# ab-berry-rev2-2.net
KiCad netlist of a schematic drawn in EAGLE
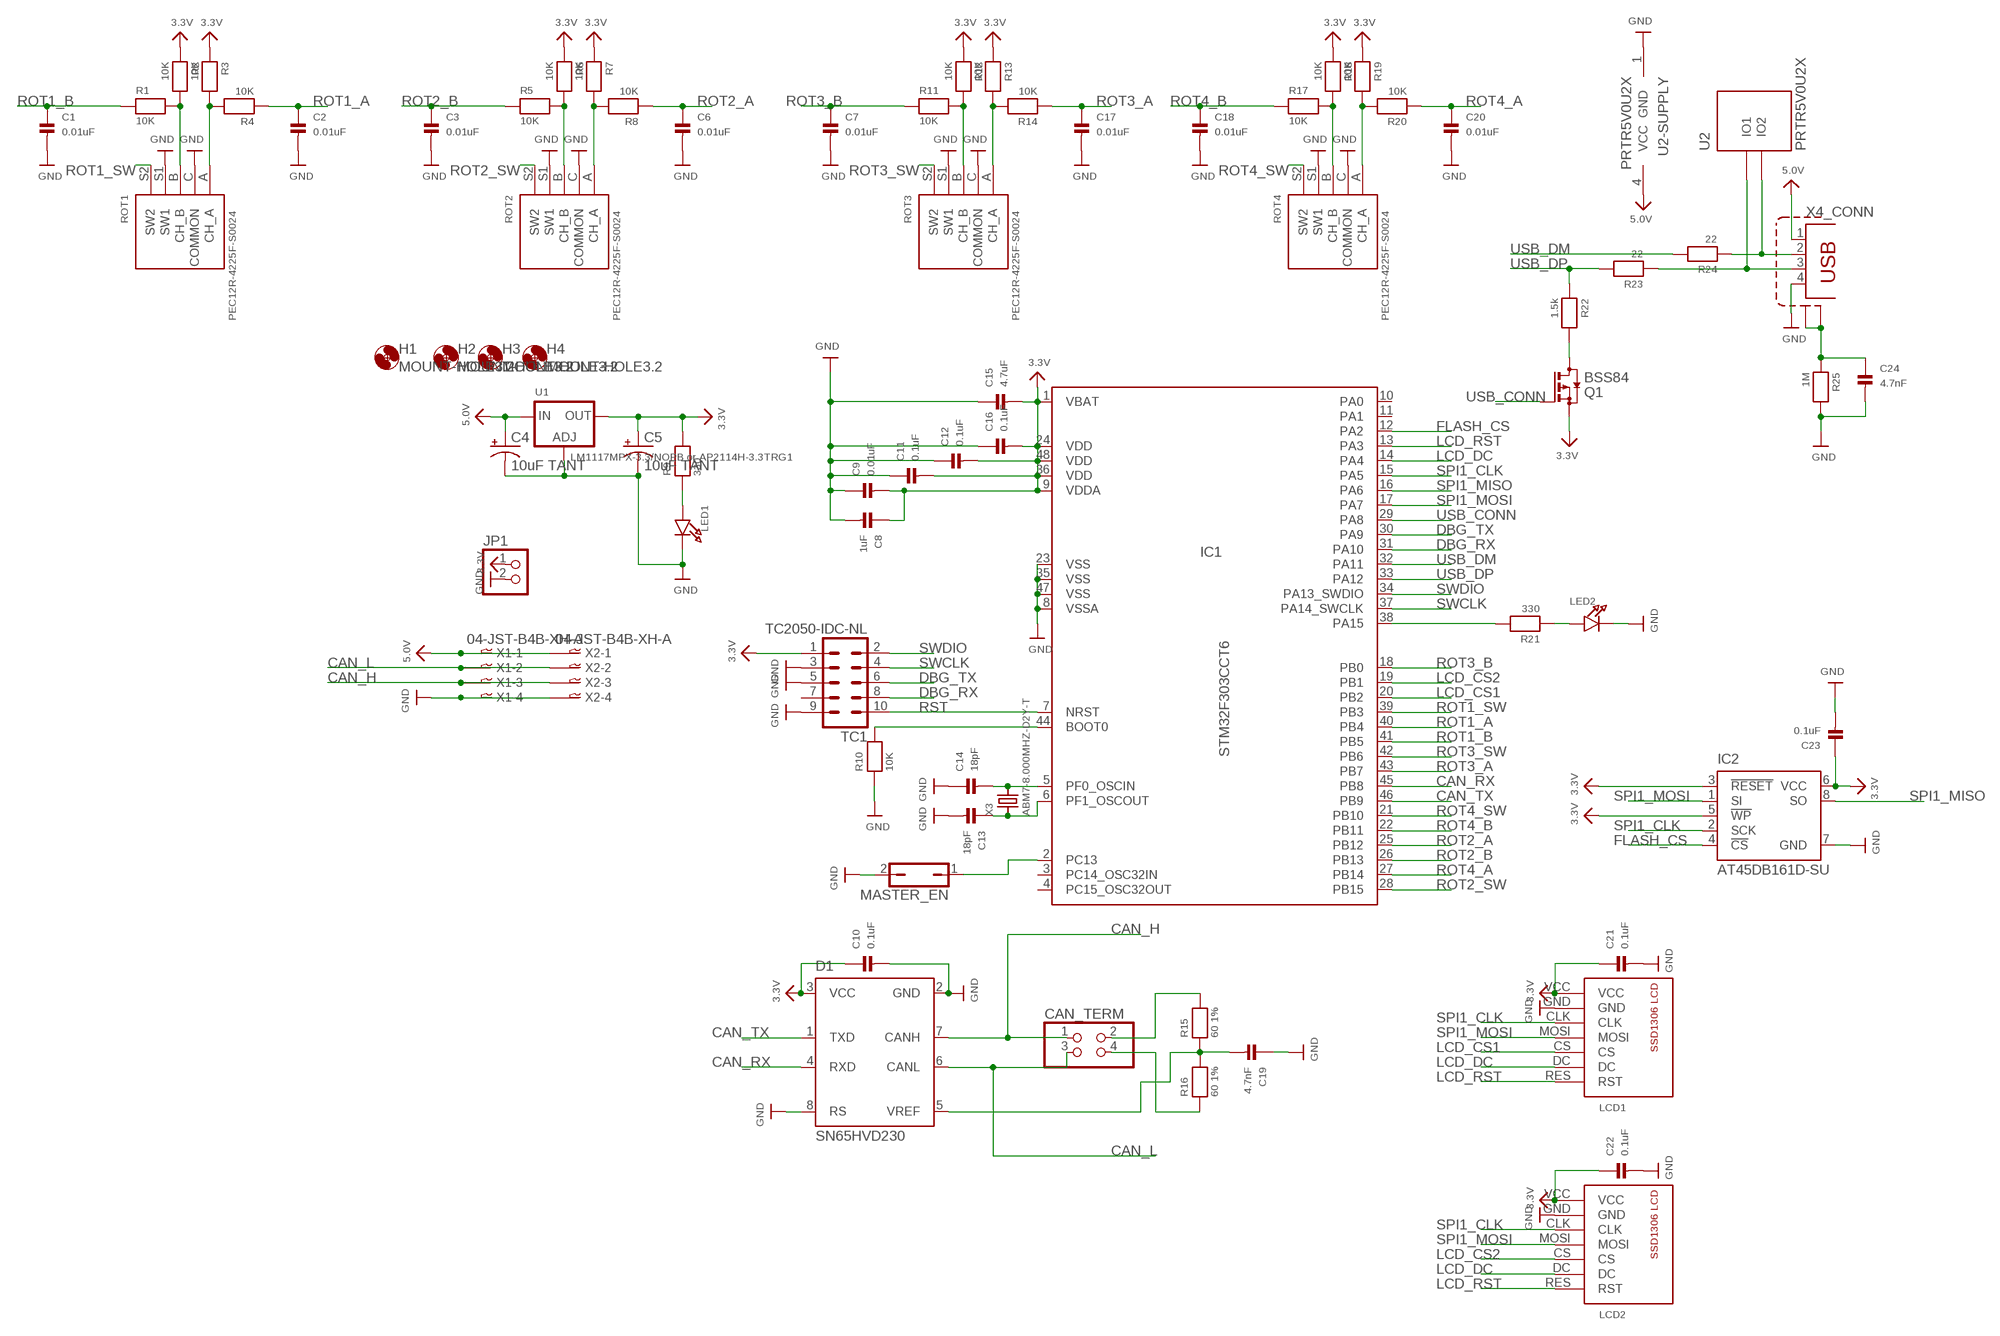
[diagram p0: schematic, sheet 1]

(export (version "E")
  (design (tool "Eeschema 10.0.6"))
  (components
    (comp (ref "C1")
      (value "0.01uF")
      (footprint "eagle-import:0603")
      (libsource (lib "eagle-import") (part "CAP_CERAMIC0603"))
    )
    (comp (ref "C2")
      (value "0.01uF")
      (footprint "eagle-import:0603")
      (libsource (lib "eagle-import") (part "CAP_CERAMIC0603"))
    )
    (comp (ref "C3")
      (value "0.01uF")
      (footprint "eagle-import:0603")
      (libsource (lib "eagle-import") (part "CAP_CERAMIC0603"))
    )
    (comp (ref "C4")
      (value "10uF TANT")
      (footprint "eagle-import:0603-POL")
      (libsource (lib "eagle-import") (part "10UF-6.3V-20%(0603)(TANT){dblquote}"))
    )
    (comp (ref "C5")
      (value "10uF TANT")
      (footprint "eagle-import:0603-POL")
      (libsource (lib "eagle-import") (part "10UF-6.3V-20%(0603)(TANT){dblquote}"))
    )
    (comp (ref "C6")
      (value "0.01uF")
      (footprint "eagle-import:0603")
      (libsource (lib "eagle-import") (part "CAP_CERAMIC0603"))
    )
    (comp (ref "C7")
      (value "0.01uF")
      (footprint "eagle-import:0603")
      (libsource (lib "eagle-import") (part "CAP_CERAMIC0603"))
    )
    (comp (ref "C8")
      (value "1uF")
      (footprint "eagle-import:0603")
      (libsource (lib "eagle-import") (part "CAP_CERAMIC0603"))
    )
    (comp (ref "C9")
      (value "0.01uF")
      (footprint "eagle-import:0603")
      (libsource (lib "eagle-import") (part "CAP_CERAMIC0603"))
    )
    (comp (ref "C10")
      (value "0.1uF")
      (footprint "eagle-import:0603")
      (libsource (lib "eagle-import") (part "CAP_CERAMIC0603"))
    )
    (comp (ref "C11")
      (value "0.1uF")
      (footprint "eagle-import:0603")
      (libsource (lib "eagle-import") (part "CAP_CERAMIC0603"))
    )
    (comp (ref "C12")
      (value "0.1uF")
      (footprint "eagle-import:0603")
      (libsource (lib "eagle-import") (part "CAP_CERAMIC0603"))
    )
    (comp (ref "C13")
      (value "18pF")
      (footprint "eagle-import:0603")
      (libsource (lib "eagle-import") (part "CAP_CERAMIC0603"))
    )
    (comp (ref "C14")
      (value "18pF")
      (footprint "eagle-import:0603")
      (libsource (lib "eagle-import") (part "CAP_CERAMIC0603"))
    )
    (comp (ref "C15")
      (value "4.7uF")
      (footprint "eagle-import:0603")
      (libsource (lib "eagle-import") (part "CAP_CERAMIC0603"))
    )
    (comp (ref "C16")
      (value "0.1uF")
      (footprint "eagle-import:0603")
      (libsource (lib "eagle-import") (part "CAP_CERAMIC0603"))
    )
    (comp (ref "C17")
      (value "0.01uF")
      (footprint "eagle-import:0603")
      (libsource (lib "eagle-import") (part "CAP_CERAMIC0603"))
    )
    (comp (ref "C18")
      (value "0.01uF")
      (footprint "eagle-import:0603")
      (libsource (lib "eagle-import") (part "CAP_CERAMIC0603"))
    )
    (comp (ref "C19")
      (value "4.7nF")
      (footprint "eagle-import:0603")
      (libsource (lib "eagle-import") (part "CAP_CERAMIC0603"))
    )
    (comp (ref "C20")
      (value "0.01uF")
      (footprint "eagle-import:0603")
      (libsource (lib "eagle-import") (part "CAP_CERAMIC0603"))
    )
    (comp (ref "C21")
      (value "0.1uF")
      (footprint "eagle-import:0603")
      (libsource (lib "eagle-import") (part "CAP_CERAMIC0603"))
    )
    (comp (ref "C22")
      (value "0.1uF")
      (footprint "eagle-import:0603")
      (libsource (lib "eagle-import") (part "CAP_CERAMIC0603"))
    )
    (comp (ref "C23")
      (value "0.1uF")
      (footprint "eagle-import:0603")
      (libsource (lib "eagle-import") (part "CAP_CERAMIC0603"))
    )
    (comp (ref "C24")
      (value "4.7nF")
      (footprint "eagle-import:0603")
      (libsource (lib "eagle-import") (part "CAP_CERAMIC0603"))
    )
    (comp (ref "CAN_TERM")
      (value "PINHD-2X2")
      (footprint "eagle-import:2X02")
      (libsource (lib "eagle-import") (part "PINHD-2X2"))
    )
    (comp (ref "D1")
      (value "SN65HVD230")
      (footprint "eagle-import:SO8")
      (libsource (lib "eagle-import") (part "SN65HVD230"))
    )
    (comp (ref "H1")
      (value "MOUNT-HOLE3.2")
      (footprint "eagle-import:3,2")
      (libsource (lib "eagle-import") (part "MOUNT-HOLE3.2"))
    )
    (comp (ref "H2")
      (value "MOUNT-HOLE3.2")
      (footprint "eagle-import:3,2")
      (libsource (lib "eagle-import") (part "MOUNT-HOLE3.2"))
    )
    (comp (ref "H3")
      (value "MOUNT-HOLE3.2")
      (footprint "eagle-import:3,2")
      (libsource (lib "eagle-import") (part "MOUNT-HOLE3.2"))
    )
    (comp (ref "H4")
      (value "MOUNT-HOLE3.2")
      (footprint "eagle-import:3,2")
      (libsource (lib "eagle-import") (part "MOUNT-HOLE3.2"))
    )
    (comp (ref "IC1")
      (value "STM32F303CCT6")
      (footprint "eagle-import:TQFP48")
      (libsource (lib "eagle-import") (part "STM32F302_F303_B_C_LQFP48"))
    )
    (comp (ref "IC2")
      (value "AT45DB161D-SU")
      (footprint "eagle-import:8S2")
      (fields (field (name "MF") "ATMEL"))
      (libsource (lib "eagle-import") (part "AT45DB161D-SU"))
    )
    (comp (ref "JP1")
      (value "PINHD-1X2")
      (footprint "eagle-import:1X02")
      (libsource (lib "eagle-import") (part "PINHD-1X2"))
    )
    (comp (ref "LCD1")
      (value "SSD1306-7PINWITHOUT-HOLES")
      (footprint "eagle-import:SSD1306-7PIN-NO-HOLES")
      (libsource (lib "eagle-import") (part "SSD1306-7PINWITHOUT-HOLES"))
    )
    (comp (ref "LCD2")
      (value "SSD1306-7PINWITHOUT-HOLES")
      (footprint "eagle-import:SSD1306-7PIN-NO-HOLES")
      (libsource (lib "eagle-import") (part "SSD1306-7PINWITHOUT-HOLES"))
    )
    (comp (ref "LED1")
      (value "LED0603")
      (footprint "eagle-import:CHIPLED_0603")
      (libsource (lib "eagle-import") (part "LED0603"))
    )
    (comp (ref "LED2")
      (value "LED0603")
      (footprint "eagle-import:CHIPLED_0603")
      (libsource (lib "eagle-import") (part "LED0603"))
    )
    (comp (ref "MASTER_EN")
      (value "JP1Q")
      (footprint "eagle-import:JP1")
      (libsource (lib "eagle-import") (part "JP1Q"))
    )
    (comp (ref "Q1")
      (value "BSS84")
      (footprint "eagle-import:SOT23")
      (libsource (lib "eagle-import") (part "BSS84"))
    )
    (comp (ref "R1")
      (value "10K")
      (footprint "eagle-import:0603")
      (libsource (lib "eagle-import") (part "RESISTOR0603"))
    )
    (comp (ref "R2")
      (value "10K")
      (footprint "eagle-import:0603")
      (libsource (lib "eagle-import") (part "RESISTOR0603"))
    )
    (comp (ref "R3")
      (value "10K")
      (footprint "eagle-import:0603")
      (libsource (lib "eagle-import") (part "RESISTOR0603"))
    )
    (comp (ref "R4")
      (value "10K")
      (footprint "eagle-import:0603")
      (libsource (lib "eagle-import") (part "RESISTOR0603"))
    )
    (comp (ref "R5")
      (value "10K")
      (footprint "eagle-import:0603")
      (libsource (lib "eagle-import") (part "RESISTOR0603"))
    )
    (comp (ref "R6")
      (value "10K")
      (footprint "eagle-import:0603")
      (libsource (lib "eagle-import") (part "RESISTOR0603"))
    )
    (comp (ref "R7")
      (value "10K")
      (footprint "eagle-import:0603")
      (libsource (lib "eagle-import") (part "RESISTOR0603"))
    )
    (comp (ref "R8")
      (value "10K")
      (footprint "eagle-import:0603")
      (libsource (lib "eagle-import") (part "RESISTOR0603"))
    )
    (comp (ref "R9")
      (value "330")
      (footprint "eagle-import:0603")
      (libsource (lib "eagle-import") (part "RESISTOR0603"))
    )
    (comp (ref "R10")
      (value "10K")
      (footprint "eagle-import:0603")
      (libsource (lib "eagle-import") (part "RESISTOR0603"))
    )
    (comp (ref "R11")
      (value "10K")
      (footprint "eagle-import:0603")
      (libsource (lib "eagle-import") (part "RESISTOR0603"))
    )
    (comp (ref "R12")
      (value "10K")
      (footprint "eagle-import:0603")
      (libsource (lib "eagle-import") (part "RESISTOR0603"))
    )
    (comp (ref "R13")
      (value "10K")
      (footprint "eagle-import:0603")
      (libsource (lib "eagle-import") (part "RESISTOR0603"))
    )
    (comp (ref "R14")
      (value "10K")
      (footprint "eagle-import:0603")
      (libsource (lib "eagle-import") (part "RESISTOR0603"))
    )
    (comp (ref "R15")
      (value "60 1%")
      (footprint "eagle-import:0603")
      (libsource (lib "eagle-import") (part "RESISTOR0603"))
    )
    (comp (ref "R16")
      (value "60 1%")
      (footprint "eagle-import:0603")
      (libsource (lib "eagle-import") (part "RESISTOR0603"))
    )
    (comp (ref "R17")
      (value "10K")
      (footprint "eagle-import:0603")
      (libsource (lib "eagle-import") (part "RESISTOR0603"))
    )
    (comp (ref "R18")
      (value "10K")
      (footprint "eagle-import:0603")
      (libsource (lib "eagle-import") (part "RESISTOR0603"))
    )
    (comp (ref "R19")
      (value "10K")
      (footprint "eagle-import:0603")
      (libsource (lib "eagle-import") (part "RESISTOR0603"))
    )
    (comp (ref "R20")
      (value "10K")
      (footprint "eagle-import:0603")
      (libsource (lib "eagle-import") (part "RESISTOR0603"))
    )
    (comp (ref "R21")
      (value "330")
      (footprint "eagle-import:0603")
      (libsource (lib "eagle-import") (part "RESISTOR0603"))
    )
    (comp (ref "R22")
      (value "1.5k")
      (footprint "eagle-import:0603")
      (libsource (lib "eagle-import") (part "RESISTOR0603"))
    )
    (comp (ref "R23")
      (value "22")
      (footprint "eagle-import:0603")
      (libsource (lib "eagle-import") (part "RESISTOR0603"))
    )
    (comp (ref "R24")
      (value "22")
      (footprint "eagle-import:0603")
      (libsource (lib "eagle-import") (part "RESISTOR0603"))
    )
    (comp (ref "R25")
      (value "1M")
      (footprint "eagle-import:0603")
      (libsource (lib "eagle-import") (part "RESISTOR0603"))
    )
    (comp (ref "ROT1")
      (value "PEC12R-4225F-S0024")
      (footprint "eagle-import:PEC111-4XXXK-SXXXX")
      (libsource (lib "eagle-import") (part "PEC11-4215K-S0024"))
    )
    (comp (ref "ROT2")
      (value "PEC12R-4225F-S0024")
      (footprint "eagle-import:PEC111-4XXXK-SXXXX")
      (libsource (lib "eagle-import") (part "PEC11-4215K-S0024"))
    )
    (comp (ref "ROT3")
      (value "PEC12R-4225F-S0024")
      (footprint "eagle-import:PEC111-4XXXK-SXXXX")
      (libsource (lib "eagle-import") (part "PEC11-4215K-S0024"))
    )
    (comp (ref "ROT4")
      (value "PEC12R-4225F-S0024")
      (footprint "eagle-import:PEC111-4XXXK-SXXXX")
      (libsource (lib "eagle-import") (part "PEC11-4215K-S0024"))
    )
    (comp (ref "TC1")
      (value "TC2050-IDC-NL")
      (footprint "eagle-import:TC2050-IDC-NL")
      (libsource (lib "eagle-import") (part "TC2050-IDC-NL"))
    )
    (comp (ref "U1")
      (value "LM1117MPX-3.3/NOPB or AP2114H-3.3TRG1")
      (footprint "eagle-import:SOT223-R")
      (fields (field (name "MPN") "LM1117MPX-3.3/NOPB"))
      (libsource (lib "eagle-import") (part "LM1117SOT223-REFLOW"))
    )
    (comp (ref "U2")
      (value "PRTR5V0U2X")
      (footprint "eagle-import:SOT-143B")
      (fields
        (field (name "MANUFACTURER") "NXP Semiconductors")
        (field (name "PART_NUMBER") "PRTR5V0U2X,215")
      )
      (libsource (lib "eagle-import") (part "PRTR5V0U2X?"))
    )
    (comp (ref "X1")
      (value "04-JST-B4B-XH-A")
      (footprint "eagle-import:B4B-XH")
      (libsource (lib "eagle-import") (part "04-JST-B4B-XH-A"))
    )
    (comp (ref "X2")
      (value "04-JST-B4B-XH-A")
      (footprint "eagle-import:B4B-XH")
      (libsource (lib "eagle-import") (part "04-JST-B4B-XH-A"))
    )
    (comp (ref "X3")
      (value "ABM7-8.000MHZ-D2Y-T")
      (footprint "eagle-import:ABM7-8.000MHZ-D2Y-T")
      (libsource (lib "eagle-import") (part "ABM7-8.000MHZ-D2Y-T"))
    )
    (comp (ref "X4")
      (value "TE-292304-1")
      (footprint "eagle-import:TE-292304-1")
      (libsource (lib "eagle-import") (part "TE-292304-1"))
    )
  )
  (nets
    (net (code "1") (name "/CAN_H") (class "Default")
      (node (ref "CAN_TERM") (pin "1") (pinfunction "1_1") (pintype "passive"))
      (node (ref "D1") (pin "7") (pinfunction "CANH_7") (pintype "bidirectional"))
      (node (ref "X1") (pin "P$3") (pinfunction "1_P$3") (pintype "passive"))
      (node (ref "X2") (pin "P$3") (pinfunction "1_P$3") (pintype "passive"))
    )
    (net (code "2") (name "/CAN_L") (class "Default")
      (node (ref "CAN_TERM") (pin "3") (pinfunction "3_3") (pintype "passive"))
      (node (ref "D1") (pin "6") (pinfunction "CANL_6") (pintype "bidirectional"))
      (node (ref "X1") (pin "P$2") (pinfunction "1_P$2") (pintype "passive"))
      (node (ref "X2") (pin "P$2") (pinfunction "1_P$2") (pintype "passive"))
    )
    (net (code "3") (name "/CAN_RX") (class "Default")
      (node (ref "D1") (pin "4") (pinfunction "RXD_4") (pintype "output"))
      (node (ref "IC1") (pin "45") (pinfunction "PB8_45") (pintype "bidirectional"))
    )
    (net (code "4") (name "/CAN_TX") (class "Default")
      (node (ref "D1") (pin "1") (pinfunction "TXD_1") (pintype "input"))
      (node (ref "IC1") (pin "46") (pinfunction "PB9_46") (pintype "bidirectional"))
    )
    (net (code "5") (name "/DBG_RX") (class "Default")
      (node (ref "IC1") (pin "31") (pinfunction "PA10_31") (pintype "bidirectional"))
      (node (ref "TC1") (pin "8") (pinfunction "8_8") (pintype "passive"))
    )
    (net (code "6") (name "/DBG_TX") (class "Default")
      (node (ref "IC1") (pin "30") (pinfunction "PA9_30") (pintype "bidirectional"))
      (node (ref "TC1") (pin "6") (pinfunction "6_6") (pintype "passive"))
    )
    (net (code "7") (name "/FLASH_CS") (class "Default")
      (node (ref "IC1") (pin "12") (pinfunction "PA2_12") (pintype "bidirectional"))
      (node (ref "IC2") (pin "4") (pinfunction "~{CS}_4") (pintype "input"))
    )
    (net (code "8") (name "/LCD_CS1") (class "Default")
      (node (ref "IC1") (pin "20") (pinfunction "PB2_20") (pintype "bidirectional"))
      (node (ref "LCD1") (pin "CS") (pinfunction "CS_CS") (pintype "bidirectional"))
    )
    (net (code "9") (name "/LCD_CS2") (class "Default")
      (node (ref "IC1") (pin "19") (pinfunction "PB1_19") (pintype "bidirectional"))
      (node (ref "LCD2") (pin "CS") (pinfunction "CS_CS") (pintype "bidirectional"))
    )
    (net (code "10") (name "/LCD_DC") (class "Default")
      (node (ref "IC1") (pin "14") (pinfunction "PA4_14") (pintype "bidirectional"))
      (node (ref "LCD1") (pin "DC") (pinfunction "DC_DC") (pintype "bidirectional"))
      (node (ref "LCD2") (pin "DC") (pinfunction "DC_DC") (pintype "bidirectional"))
    )
    (net (code "11") (name "/LCD_RST") (class "Default")
      (node (ref "IC1") (pin "13") (pinfunction "PA3_13") (pintype "bidirectional"))
      (node (ref "LCD1") (pin "RES") (pinfunction "RST_RES") (pintype "bidirectional"))
      (node (ref "LCD2") (pin "RES") (pinfunction "RST_RES") (pintype "bidirectional"))
    )
    (net (code "12") (name "/ROT1_A") (class "Default")
      (node (ref "C2") (pin "1") (pinfunction "P$1_1") (pintype "passive"))
      (node (ref "IC1") (pin "40") (pinfunction "PB4_40") (pintype "input"))
      (node (ref "R4") (pin "1") (pinfunction "1_1") (pintype "passive"))
    )
    (net (code "13") (name "/ROT1_B") (class "Default")
      (node (ref "C1") (pin "1") (pinfunction "P$1_1") (pintype "passive"))
      (node (ref "IC1") (pin "41") (pinfunction "PB5_41") (pintype "bidirectional"))
      (node (ref "R1") (pin "1") (pinfunction "1_1") (pintype "passive"))
    )
    (net (code "14") (name "/ROT1_SW") (class "Default")
      (node (ref "IC1") (pin "39") (pinfunction "PB3_39") (pintype "output"))
      (node (ref "ROT1") (pin "S2") (pinfunction "SW2_S2") (pintype "bidirectional"))
    )
    (net (code "15") (name "/ROT2_A") (class "Default")
      (node (ref "C6") (pin "1") (pinfunction "P$1_1") (pintype "passive"))
      (node (ref "IC1") (pin "25") (pinfunction "PB12_25") (pintype "bidirectional"))
      (node (ref "R8") (pin "1") (pinfunction "1_1") (pintype "passive"))
    )
    (net (code "16") (name "/ROT2_B") (class "Default")
      (node (ref "C3") (pin "1") (pinfunction "P$1_1") (pintype "passive"))
      (node (ref "IC1") (pin "26") (pinfunction "PB13_26") (pintype "bidirectional"))
      (node (ref "R5") (pin "1") (pinfunction "1_1") (pintype "passive"))
    )
    (net (code "17") (name "/ROT2_SW") (class "Default")
      (node (ref "IC1") (pin "28") (pinfunction "PB15_28") (pintype "bidirectional"))
      (node (ref "ROT2") (pin "S2") (pinfunction "SW2_S2") (pintype "bidirectional"))
    )
    (net (code "18") (name "/ROT3_A") (class "Default")
      (node (ref "C17") (pin "1") (pinfunction "P$1_1") (pintype "passive"))
      (node (ref "IC1") (pin "43") (pinfunction "PB7_43") (pintype "bidirectional"))
      (node (ref "R14") (pin "1") (pinfunction "1_1") (pintype "passive"))
    )
    (net (code "19") (name "/ROT3_B") (class "Default")
      (node (ref "C7") (pin "1") (pinfunction "P$1_1") (pintype "passive"))
      (node (ref "IC1") (pin "18") (pinfunction "PB0_18") (pintype "bidirectional"))
      (node (ref "R11") (pin "1") (pinfunction "1_1") (pintype "passive"))
    )
    (net (code "20") (name "/ROT3_SW") (class "Default")
      (node (ref "IC1") (pin "42") (pinfunction "PB6_42") (pintype "bidirectional"))
      (node (ref "ROT3") (pin "S2") (pinfunction "SW2_S2") (pintype "bidirectional"))
    )
    (net (code "21") (name "/ROT4_A") (class "Default")
      (node (ref "C20") (pin "1") (pinfunction "P$1_1") (pintype "passive"))
      (node (ref "IC1") (pin "27") (pinfunction "PB14_27") (pintype "bidirectional"))
      (node (ref "R20") (pin "1") (pinfunction "1_1") (pintype "passive"))
    )
    (net (code "22") (name "/ROT4_B") (class "Default")
      (node (ref "C18") (pin "1") (pinfunction "P$1_1") (pintype "passive"))
      (node (ref "IC1") (pin "22") (pinfunction "PB11_22") (pintype "bidirectional"))
      (node (ref "R17") (pin "1") (pinfunction "1_1") (pintype "passive"))
    )
    (net (code "23") (name "/ROT4_SW") (class "Default")
      (node (ref "IC1") (pin "21") (pinfunction "PB10_21") (pintype "bidirectional"))
      (node (ref "ROT4") (pin "S2") (pinfunction "SW2_S2") (pintype "bidirectional"))
    )
    (net (code "24") (name "/RST") (class "Default")
      (node (ref "IC1") (pin "7") (pinfunction "NRST_7") (pintype "input"))
      (node (ref "TC1") (pin "10") (pinfunction "10_10") (pintype "passive"))
    )
    (net (code "25") (name "/SPI1_CLK") (class "Default")
      (node (ref "IC1") (pin "15") (pinfunction "PA5_15") (pintype "bidirectional"))
      (node (ref "IC2") (pin "2") (pinfunction "SCK_2") (pintype "input"))
      (node (ref "LCD1") (pin "CLK") (pinfunction "CLK_CLK") (pintype "bidirectional"))
      (node (ref "LCD2") (pin "CLK") (pinfunction "CLK_CLK") (pintype "bidirectional"))
    )
    (net (code "26") (name "/SPI1_MISO") (class "Default")
      (node (ref "IC1") (pin "16") (pinfunction "PA6_16") (pintype "bidirectional"))
      (node (ref "IC2") (pin "8") (pinfunction "SO_8") (pintype "output"))
    )
    (net (code "27") (name "/SPI1_MOSI") (class "Default")
      (node (ref "IC1") (pin "17") (pinfunction "PA7_17") (pintype "bidirectional"))
      (node (ref "IC2") (pin "1") (pinfunction "SI_1") (pintype "input"))
      (node (ref "LCD1") (pin "MOSI") (pinfunction "MOSI_MOSI") (pintype "bidirectional"))
      (node (ref "LCD2") (pin "MOSI") (pinfunction "MOSI_MOSI") (pintype "bidirectional"))
    )
    (net (code "28") (name "/SWCLK") (class "Default")
      (node (ref "IC1") (pin "37") (pinfunction "PA14_SWCLK_37") (pintype "input"))
      (node (ref "TC1") (pin "4") (pinfunction "4_4") (pintype "passive"))
    )
    (net (code "29") (name "/SWDIO") (class "Default")
      (node (ref "IC1") (pin "34") (pinfunction "PA13_SWDIO_34") (pintype "input"))
      (node (ref "TC1") (pin "2") (pinfunction "2_2") (pintype "passive"))
    )
    (net (code "30") (name "/USB_CONN") (class "Default")
      (node (ref "IC1") (pin "29") (pinfunction "PA8_29") (pintype "bidirectional"))
      (node (ref "Q1") (pin "1") (pinfunction "G_1") (pintype "passive"))
    )
    (net (code "31") (name "/USB_DM") (class "Default")
      (node (ref "IC1") (pin "32") (pinfunction "PA11_32") (pintype "bidirectional"))
      (node (ref "R24") (pin "2") (pinfunction "2_2") (pintype "passive"))
    )
    (net (code "32") (name "/USB_DP") (class "Default")
      (node (ref "IC1") (pin "33") (pinfunction "PA12_33") (pintype "bidirectional"))
      (node (ref "R22") (pin "1") (pinfunction "1_1") (pintype "passive"))
      (node (ref "R23") (pin "2") (pinfunction "2_2") (pintype "passive"))
    )
    (net (code "33") (name "3.3V") (class "Default")
      (node (ref "C10") (pin "1") (pinfunction "P$1_1") (pintype "passive"))
      (node (ref "C11") (pin "2") (pinfunction "P$2_2") (pintype "passive"))
      (node (ref "C12") (pin "2") (pinfunction "P$2_2") (pintype "passive"))
      (node (ref "C15") (pin "2") (pinfunction "P$2_2") (pintype "passive"))
      (node (ref "C16") (pin "2") (pinfunction "P$2_2") (pintype "passive"))
      (node (ref "C21") (pin "1") (pinfunction "P$1_1") (pintype "passive"))
      (node (ref "C22") (pin "1") (pinfunction "P$1_1") (pintype "passive"))
      (node (ref "C23") (pin "1") (pinfunction "P$1_1") (pintype "passive"))
      (node (ref "C5") (pin "A") (pinfunction "+_A") (pintype "passive"))
      (node (ref "C8") (pin "1") (pinfunction "P$1_1") (pintype "passive"))
      (node (ref "C9") (pin "2") (pinfunction "P$2_2") (pintype "passive"))
      (node (ref "D1") (pin "3") (pinfunction "VCC_3") (pintype "power_in"))
      (node (ref "IC1") (pin "1") (pinfunction "VBAT_1") (pintype "passive"))
      (node (ref "IC1") (pin "24") (pinfunction "VDD_24") (pintype "power_in"))
      (node (ref "IC1") (pin "36") (pinfunction "VDD_36") (pintype "power_in"))
      (node (ref "IC1") (pin "48") (pinfunction "VDD_48") (pintype "power_in"))
      (node (ref "IC1") (pin "9") (pinfunction "VDDA_9") (pintype "power_in"))
      (node (ref "IC2") (pin "3") (pinfunction "~{RESET}_3") (pintype "input"))
      (node (ref "IC2") (pin "5") (pinfunction "~{WP}_5") (pintype "input"))
      (node (ref "IC2") (pin "6") (pinfunction "VCC_6") (pintype "power_in"))
      (node (ref "JP1") (pin "1") (pinfunction "1_1") (pintype "passive"))
      (node (ref "LCD1") (pin "VCC") (pinfunction "VCC_VCC") (pintype "bidirectional"))
      (node (ref "LCD2") (pin "VCC") (pinfunction "VCC_VCC") (pintype "bidirectional"))
      (node (ref "Q1") (pin "2") (pinfunction "S_2") (pintype "passive"))
      (node (ref "R12") (pin "1") (pinfunction "1_1") (pintype "passive"))
      (node (ref "R13") (pin "1") (pinfunction "1_1") (pintype "passive"))
      (node (ref "R18") (pin "1") (pinfunction "1_1") (pintype "passive"))
      (node (ref "R19") (pin "1") (pinfunction "1_1") (pintype "passive"))
      (node (ref "R2") (pin "1") (pinfunction "1_1") (pintype "passive"))
      (node (ref "R3") (pin "1") (pinfunction "1_1") (pintype "passive"))
      (node (ref "R6") (pin "1") (pinfunction "1_1") (pintype "passive"))
      (node (ref "R7") (pin "1") (pinfunction "1_1") (pintype "passive"))
      (node (ref "R9") (pin "2") (pinfunction "2_2") (pintype "passive"))
      (node (ref "TC1") (pin "1") (pinfunction "1_1") (pintype "passive"))
      (node (ref "U1") (pin "2") (pinfunction "OUT_2") (pintype "passive"))
    )
    (net (code "34") (name "5.0V") (class "Default")
      (node (ref "C4") (pin "A") (pinfunction "+_A") (pintype "passive"))
      (node (ref "U1") (pin "3") (pinfunction "IN_3") (pintype "input"))
      (node (ref "U2") (pin "4") (pinfunction "VCC_4") (pintype "bidirectional"))
      (node (ref "X1") (pin "P$1") (pinfunction "1_P$1") (pintype "passive"))
      (node (ref "X2") (pin "P$1") (pinfunction "1_P$1") (pintype "passive"))
      (node (ref "X4") (pin "1") (pinfunction "1_1") (pintype "bidirectional"))
    )
    (net (code "35") (name "GND") (class "Default")
      (node (ref "C1") (pin "2") (pinfunction "P$2_2") (pintype "passive"))
      (node (ref "C10") (pin "2") (pinfunction "P$2_2") (pintype "passive"))
      (node (ref "C11") (pin "1") (pinfunction "P$1_1") (pintype "passive"))
      (node (ref "C12") (pin "1") (pinfunction "P$1_1") (pintype "passive"))
      (node (ref "C13") (pin "2") (pinfunction "P$2_2") (pintype "passive"))
      (node (ref "C14") (pin "1") (pinfunction "P$1_1") (pintype "passive"))
      (node (ref "C15") (pin "1") (pinfunction "P$1_1") (pintype "passive"))
      (node (ref "C16") (pin "1") (pinfunction "P$1_1") (pintype "passive"))
      (node (ref "C17") (pin "2") (pinfunction "P$2_2") (pintype "passive"))
      (node (ref "C18") (pin "2") (pinfunction "P$2_2") (pintype "passive"))
      (node (ref "C19") (pin "1") (pinfunction "P$1_1") (pintype "passive"))
      (node (ref "C2") (pin "2") (pinfunction "P$2_2") (pintype "passive"))
      (node (ref "C20") (pin "2") (pinfunction "P$2_2") (pintype "passive"))
      (node (ref "C21") (pin "2") (pinfunction "P$2_2") (pintype "passive"))
      (node (ref "C22") (pin "2") (pinfunction "P$2_2") (pintype "passive"))
      (node (ref "C23") (pin "2") (pinfunction "P$2_2") (pintype "passive"))
      (node (ref "C24") (pin "2") (pinfunction "P$2_2") (pintype "passive"))
      (node (ref "C3") (pin "2") (pinfunction "P$2_2") (pintype "passive"))
      (node (ref "C4") (pin "K") (pinfunction "-_K") (pintype "passive"))
      (node (ref "C5") (pin "K") (pinfunction "-_K") (pintype "passive"))
      (node (ref "C6") (pin "2") (pinfunction "P$2_2") (pintype "passive"))
      (node (ref "C7") (pin "2") (pinfunction "P$2_2") (pintype "passive"))
      (node (ref "C8") (pin "2") (pinfunction "P$2_2") (pintype "passive"))
      (node (ref "C9") (pin "1") (pinfunction "P$1_1") (pintype "passive"))
      (node (ref "D1") (pin "2") (pinfunction "GND_2") (pintype "power_in"))
      (node (ref "D1") (pin "8") (pinfunction "RS_8") (pintype "input"))
      (node (ref "IC1") (pin "23") (pinfunction "VSS_23") (pintype "power_in"))
      (node (ref "IC1") (pin "35") (pinfunction "VSS_35") (pintype "power_in"))
      (node (ref "IC1") (pin "47") (pinfunction "VSS_47") (pintype "power_in"))
      (node (ref "IC1") (pin "8") (pinfunction "VSSA_8") (pintype "power_in"))
      (node (ref "IC2") (pin "7") (pinfunction "GND_7") (pintype "power_in"))
      (node (ref "JP1") (pin "2") (pinfunction "2_2") (pintype "passive"))
      (node (ref "LCD1") (pin "GND") (pinfunction "GND_GND") (pintype "bidirectional"))
      (node (ref "LCD2") (pin "GND") (pinfunction "GND_GND") (pintype "bidirectional"))
      (node (ref "LED1") (pin "C") (pinfunction "C_C") (pintype "passive"))
      (node (ref "LED2") (pin "C") (pinfunction "C_C") (pintype "passive"))
      (node (ref "MASTER_EN") (pin "2") (pinfunction "2_2") (pintype "passive"))
      (node (ref "R10") (pin "1") (pinfunction "1_1") (pintype "passive"))
      (node (ref "R25") (pin "2") (pinfunction "2_2") (pintype "passive"))
      (node (ref "ROT1") (pin "C") (pinfunction "COMMON_C") (pintype "input"))
      (node (ref "ROT1") (pin "S1") (pinfunction "SW1_S1") (pintype "bidirectional"))
      (node (ref "ROT2") (pin "C") (pinfunction "COMMON_C") (pintype "input"))
      (node (ref "ROT2") (pin "S1") (pinfunction "SW1_S1") (pintype "bidirectional"))
      (node (ref "ROT3") (pin "C") (pinfunction "COMMON_C") (pintype "input"))
      (node (ref "ROT3") (pin "S1") (pinfunction "SW1_S1") (pintype "bidirectional"))
      (node (ref "ROT4") (pin "C") (pinfunction "COMMON_C") (pintype "input"))
      (node (ref "ROT4") (pin "S1") (pinfunction "SW1_S1") (pintype "bidirectional"))
      (node (ref "TC1") (pin "3") (pinfunction "3_3") (pintype "passive"))
      (node (ref "TC1") (pin "5") (pinfunction "5_5") (pintype "passive"))
      (node (ref "TC1") (pin "9") (pinfunction "9_9") (pintype "passive"))
      (node (ref "U1") (pin "1") (pinfunction "ADJ_1") (pintype "input"))
      (node (ref "U2") (pin "1") (pinfunction "GND_1") (pintype "bidirectional"))
      (node (ref "X1") (pin "P$4") (pinfunction "1_P$4") (pintype "passive"))
      (node (ref "X2") (pin "P$4") (pinfunction "1_P$4") (pintype "passive"))
      (node (ref "X4") (pin "4") (pinfunction "4_4") (pintype "bidirectional"))
    )
    (net (code "36") (name "Net-(C13-P$1)") (class "Default")
      (node (ref "C13") (pin "1") (pinfunction "P$1_1") (pintype "passive"))
      (node (ref "IC1") (pin "6") (pinfunction "PF1_OSCOUT_6") (pintype "bidirectional"))
      (node (ref "X3") (pin "P$1") (pinfunction "1_P$1") (pintype "passive"))
    )
    (net (code "37") (name "Net-(C14-P$2)") (class "Default")
      (node (ref "C14") (pin "2") (pinfunction "P$2_2") (pintype "passive"))
      (node (ref "IC1") (pin "5") (pinfunction "PF0_OSCIN_5") (pintype "bidirectional"))
      (node (ref "X3") (pin "P$2") (pinfunction "2_P$2") (pintype "passive"))
    )
    (net (code "38") (name "Net-(C19-P$2)") (class "Default")
      (node (ref "C19") (pin "2") (pinfunction "P$2_2") (pintype "passive"))
      (node (ref "D1") (pin "5") (pinfunction "VREF_5") (pintype "output"))
      (node (ref "R15") (pin "1") (pinfunction "1_1") (pintype "passive"))
      (node (ref "R16") (pin "2") (pinfunction "2_2") (pintype "passive"))
    )
    (net (code "39") (name "Net-(C24-P$1)") (class "Default")
      (node (ref "C24") (pin "1") (pinfunction "P$1_1") (pintype "passive"))
      (node (ref "R25") (pin "1") (pinfunction "1_1") (pintype "passive"))
      (node (ref "X4") (pin "P$1") (pinfunction "S1_P$1") (pintype "passive"))
      (node (ref "X4") (pin "P$2") (pinfunction "S2_P$2") (pintype "passive"))
    )
    (net (code "40") (name "Net-(CAN_TERM-Pad2)") (class "Default")
      (node (ref "CAN_TERM") (pin "2") (pinfunction "2_2") (pintype "passive"))
      (node (ref "R15") (pin "2") (pinfunction "2_2") (pintype "passive"))
    )
    (net (code "41") (name "Net-(CAN_TERM-Pad4)") (class "Default")
      (node (ref "CAN_TERM") (pin "4") (pinfunction "4_4") (pintype "passive"))
      (node (ref "R16") (pin "1") (pinfunction "1_1") (pintype "passive"))
    )
    (net (code "42") (name "Net-(IC1-BOOT0)") (class "Default")
      (node (ref "IC1") (pin "44") (pinfunction "BOOT0_44") (pintype "input"))
      (node (ref "R10") (pin "2") (pinfunction "2_2") (pintype "passive"))
    )
    (net (code "43") (name "Net-(IC1-PA15)") (class "Default")
      (node (ref "IC1") (pin "38") (pinfunction "PA15_38") (pintype "input"))
      (node (ref "R21") (pin "2") (pinfunction "2_2") (pintype "passive"))
    )
    (net (code "44") (name "Net-(IC1-PC13)") (class "Default")
      (node (ref "IC1") (pin "2") (pinfunction "PC13_2") (pintype "bidirectional"))
      (node (ref "MASTER_EN") (pin "1") (pinfunction "1_1") (pintype "passive"))
    )
    (net (code "45") (name "Net-(LED1-PadA)") (class "Default")
      (node (ref "LED1") (pin "A") (pinfunction "A_A") (pintype "passive"))
      (node (ref "R9") (pin "1") (pinfunction "1_1") (pintype "passive"))
    )
    (net (code "46") (name "Net-(LED2-PadA)") (class "Default")
      (node (ref "LED2") (pin "A") (pinfunction "A_A") (pintype "passive"))
      (node (ref "R21") (pin "1") (pinfunction "1_1") (pintype "passive"))
    )
    (net (code "47") (name "Net-(Q1-D)") (class "Default")
      (node (ref "Q1") (pin "3") (pinfunction "D_3") (pintype "passive"))
      (node (ref "R22") (pin "2") (pinfunction "2_2") (pintype "passive"))
    )
    (net (code "48") (name "Net-(ROT1-CH_A)") (class "Default")
      (node (ref "R3") (pin "2") (pinfunction "2_2") (pintype "passive"))
      (node (ref "R4") (pin "2") (pinfunction "2_2") (pintype "passive"))
      (node (ref "ROT1") (pin "A") (pinfunction "CH_A_A") (pintype "output"))
    )
    (net (code "49") (name "Net-(ROT1-CH_B)") (class "Default")
      (node (ref "R1") (pin "2") (pinfunction "2_2") (pintype "passive"))
      (node (ref "R2") (pin "2") (pinfunction "2_2") (pintype "passive"))
      (node (ref "ROT1") (pin "B") (pinfunction "CH_B_B") (pintype "output"))
    )
    (net (code "50") (name "Net-(ROT2-CH_A)") (class "Default")
      (node (ref "R7") (pin "2") (pinfunction "2_2") (pintype "passive"))
      (node (ref "R8") (pin "2") (pinfunction "2_2") (pintype "passive"))
      (node (ref "ROT2") (pin "A") (pinfunction "CH_A_A") (pintype "output"))
    )
    (net (code "51") (name "Net-(ROT2-CH_B)") (class "Default")
      (node (ref "R5") (pin "2") (pinfunction "2_2") (pintype "passive"))
      (node (ref "R6") (pin "2") (pinfunction "2_2") (pintype "passive"))
      (node (ref "ROT2") (pin "B") (pinfunction "CH_B_B") (pintype "output"))
    )
    (net (code "52") (name "Net-(ROT3-CH_A)") (class "Default")
      (node (ref "R13") (pin "2") (pinfunction "2_2") (pintype "passive"))
      (node (ref "R14") (pin "2") (pinfunction "2_2") (pintype "passive"))
      (node (ref "ROT3") (pin "A") (pinfunction "CH_A_A") (pintype "output"))
    )
    (net (code "53") (name "Net-(ROT3-CH_B)") (class "Default")
      (node (ref "R11") (pin "2") (pinfunction "2_2") (pintype "passive"))
      (node (ref "R12") (pin "2") (pinfunction "2_2") (pintype "passive"))
      (node (ref "ROT3") (pin "B") (pinfunction "CH_B_B") (pintype "output"))
    )
    (net (code "54") (name "Net-(ROT4-CH_A)") (class "Default")
      (node (ref "R19") (pin "2") (pinfunction "2_2") (pintype "passive"))
      (node (ref "R20") (pin "2") (pinfunction "2_2") (pintype "passive"))
      (node (ref "ROT4") (pin "A") (pinfunction "CH_A_A") (pintype "output"))
    )
    (net (code "55") (name "Net-(ROT4-CH_B)") (class "Default")
      (node (ref "R17") (pin "2") (pinfunction "2_2") (pintype "passive"))
      (node (ref "R18") (pin "2") (pinfunction "2_2") (pintype "passive"))
      (node (ref "ROT4") (pin "B") (pinfunction "CH_B_B") (pintype "output"))
    )
    (net (code "56") (name "Net-(U2B-IO1)") (class "Default")
      (node (ref "R23") (pin "1") (pinfunction "1_1") (pintype "passive"))
      (node (ref "U2") (pin "2") (pinfunction "IO1_2") (pintype "bidirectional"))
      (node (ref "X4") (pin "3") (pinfunction "3_3") (pintype "bidirectional"))
    )
    (net (code "57") (name "Net-(U2B-IO2)") (class "Default")
      (node (ref "R24") (pin "1") (pinfunction "1_1") (pintype "passive"))
      (node (ref "U2") (pin "3") (pinfunction "IO2_3") (pintype "bidirectional"))
      (node (ref "X4") (pin "2") (pinfunction "2_2") (pintype "bidirectional"))
    )
    (net (code "58") (name "unconnected-(IC1-PA0-Pad10)") (class "Default")
      (node (ref "IC1") (pin "10") (pinfunction "PA0_10") (pintype "bidirectional"))
    )
    (net (code "59") (name "unconnected-(IC1-PA1-Pad11)") (class "Default")
      (node (ref "IC1") (pin "11") (pinfunction "PA1_11") (pintype "bidirectional"))
    )
    (net (code "60") (name "unconnected-(IC1-PC14_OSC32IN-Pad3)") (class "Default")
      (node (ref "IC1") (pin "3") (pinfunction "PC14_OSC32IN_3") (pintype "bidirectional"))
    )
    (net (code "61") (name "unconnected-(IC1-PC15_OSC32OUT-Pad4)") (class "Default")
      (node (ref "IC1") (pin "4") (pinfunction "PC15_OSC32OUT_4") (pintype "bidirectional"))
    )
    (net (code "62") (name "unconnected-(TC1-Pad7)") (class "Default")
      (node (ref "TC1") (pin "7") (pinfunction "7_7") (pintype "passive"))
    )
  )
)
